# E-meter.net
KiCad netlist of a schematic drawn in EAGLE
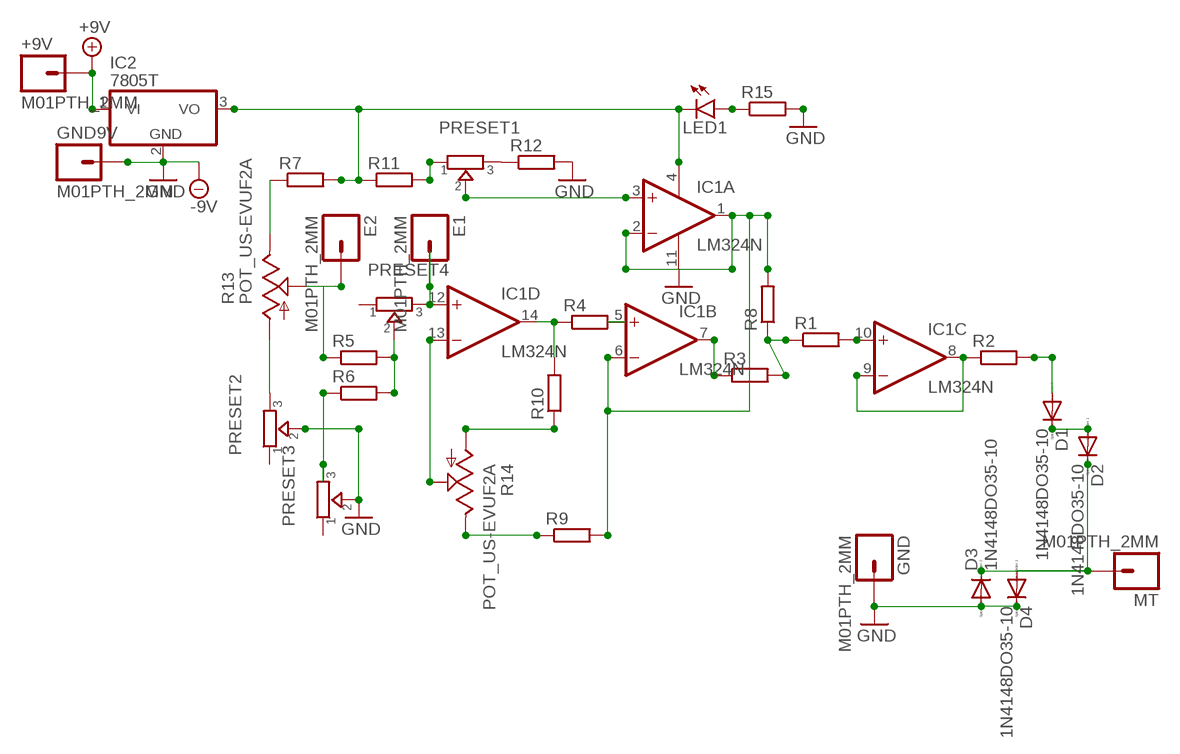
[diagram p0: schematic, sheet 1]

(export (version "E")
  (design (tool "Eeschema 10.0.6"))
  (components
    (comp (ref "+9V")
      (value "M01PTH_2MM")
      (footprint "eagle-import:1X01_2MM")
      (libsource (lib "eagle-import") (part "M01PTH_2MM"))
    )
    (comp (ref "D1")
      (value "1N4148DO35-10")
      (footprint "eagle-import:DO35-10")
      (libsource (lib "eagle-import") (part "1N4148DO35-10"))
    )
    (comp (ref "D2")
      (value "1N4148DO35-10")
      (footprint "eagle-import:DO35-10")
      (libsource (lib "eagle-import") (part "1N4148DO35-10"))
    )
    (comp (ref "D3")
      (value "1N4148DO35-10")
      (footprint "eagle-import:DO35-10")
      (libsource (lib "eagle-import") (part "1N4148DO35-10"))
    )
    (comp (ref "D4")
      (value "1N4148DO35-10")
      (footprint "eagle-import:DO35-10")
      (libsource (lib "eagle-import") (part "1N4148DO35-10"))
    )
    (comp (ref "E1")
      (value "M01PTH_2MM")
      (footprint "eagle-import:1X01_2MM")
      (libsource (lib "eagle-import") (part "M01PTH_2MM"))
    )
    (comp (ref "E2")
      (value "M01PTH_2MM")
      (footprint "eagle-import:1X01_2MM")
      (libsource (lib "eagle-import") (part "M01PTH_2MM"))
    )
    (comp (ref "GND")
      (value "M01PTH_2MM")
      (footprint "eagle-import:1X01_2MM")
      (libsource (lib "eagle-import") (part "M01PTH_2MM"))
    )
    (comp (ref "GND9V")
      (value "M01PTH_2MM")
      (footprint "eagle-import:1X01_2MM")
      (libsource (lib "eagle-import") (part "M01PTH_2MM"))
    )
    (comp (ref "IC1")
      (value "LM324N")
      (footprint "eagle-import:DIL14")
      (libsource (lib "eagle-import") (part "LM324N"))
    )
    (comp (ref "IC2")
      (value "7805T")
      (footprint "eagle-import:TO220H")
      (libsource (lib "eagle-import") (part "78T05"))
    )
    (comp (ref "LED1")
      (value "LED5MM")
      (footprint "eagle-import:LED5MM")
      (libsource (lib "eagle-import") (part "LED5MM"))
    )
    (comp (ref "MT")
      (value "M01PTH_2MM")
      (footprint "eagle-import:1X01_2MM")
      (libsource (lib "eagle-import") (part "M01PTH_2MM"))
    )
    (comp (ref "PRESET1")
      (value "TRIMMER-3306F")
      (footprint "eagle-import:TRIMMER_3306F")
      (libsource (lib "eagle-import") (part "TRIMMER-3306F"))
    )
    (comp (ref "PRESET2")
      (value "TRIMMER-3306F")
      (footprint "eagle-import:TRIMMER_3306F")
      (libsource (lib "eagle-import") (part "TRIMMER-3306F"))
    )
    (comp (ref "PRESET3")
      (value "TRIMMER-3306F")
      (footprint "eagle-import:TRIMMER_3306F")
      (libsource (lib "eagle-import") (part "TRIMMER-3306F"))
    )
    (comp (ref "PRESET4")
      (value "TRIMMER-3306F")
      (footprint "eagle-import:TRIMMER_3306F")
      (libsource (lib "eagle-import") (part "TRIMMER-3306F"))
    )
    (comp (ref "R1")
      (value "R-EU_0207/10")
      (footprint "eagle-import:0207_10")
      (libsource (lib "eagle-import") (part "R-EU_0207/10"))
    )
    (comp (ref "R2")
      (value "R-EU_0207/10")
      (footprint "eagle-import:0207_10")
      (libsource (lib "eagle-import") (part "R-EU_0207/10"))
    )
    (comp (ref "R3")
      (value "R-EU_0207/10")
      (footprint "eagle-import:0207_10")
      (libsource (lib "eagle-import") (part "R-EU_0207/10"))
    )
    (comp (ref "R4")
      (value "R-EU_0207/10")
      (footprint "eagle-import:0207_10")
      (libsource (lib "eagle-import") (part "R-EU_0207/10"))
    )
    (comp (ref "R5")
      (value "R-EU_0207/10")
      (footprint "eagle-import:0207_10")
      (libsource (lib "eagle-import") (part "R-EU_0207/10"))
    )
    (comp (ref "R6")
      (value "R-EU_0207/10")
      (footprint "eagle-import:0207_10")
      (libsource (lib "eagle-import") (part "R-EU_0207/10"))
    )
    (comp (ref "R7")
      (value "R-EU_0207/10")
      (footprint "eagle-import:0207_10")
      (libsource (lib "eagle-import") (part "R-EU_0207/10"))
    )
    (comp (ref "R8")
      (value "R-EU_0207/10")
      (footprint "eagle-import:0207_10")
      (libsource (lib "eagle-import") (part "R-EU_0207/10"))
    )
    (comp (ref "R9")
      (value "R-EU_0207/10")
      (footprint "eagle-import:0207_10")
      (libsource (lib "eagle-import") (part "R-EU_0207/10"))
    )
    (comp (ref "R10")
      (value "R-EU_0207/10")
      (footprint "eagle-import:0207_10")
      (libsource (lib "eagle-import") (part "R-EU_0207/10"))
    )
    (comp (ref "R11")
      (value "R-EU_0207/10")
      (footprint "eagle-import:0207_10")
      (libsource (lib "eagle-import") (part "R-EU_0207/10"))
    )
    (comp (ref "R12")
      (value "R-EU_0207/10")
      (footprint "eagle-import:0207_10")
      (libsource (lib "eagle-import") (part "R-EU_0207/10"))
    )
    (comp (ref "R13")
      (value "POT_US-EVUF2A")
      (footprint "eagle-import:POT_EVUF")
      (libsource (lib "eagle-import") (part "POT_US-EVUAF2"))
    )
    (comp (ref "R14")
      (value "POT_US-EVUF2A")
      (footprint "eagle-import:POT_EVUF")
      (libsource (lib "eagle-import") (part "POT_US-EVUAF2"))
    )
    (comp (ref "R15")
      (value "R-EU_0207/10")
      (footprint "eagle-import:0207_10")
      (libsource (lib "eagle-import") (part "R-EU_0207/10"))
    )
  )
  (nets
    (net (code "1") (name "+9V") (class "Default")
      (node (ref "+9V") (pin "1") (pinfunction "1_1") (pintype "passive"))
      (node (ref "IC2") (pin "1") (pinfunction "VI_1") (pintype "input"))
    )
    (net (code "2") (name "-9V") (class "Default")
      (node (ref "D3") (pin "A") (pinfunction "A_A") (pintype "passive"))
      (node (ref "D4") (pin "C") (pinfunction "C_C") (pintype "passive"))
      (node (ref "GND") (pin "1") (pinfunction "1_1") (pintype "passive"))
      (node (ref "GND9V") (pin "1") (pinfunction "1_1") (pintype "passive"))
      (node (ref "IC1") (pin "11") (pinfunction "V-_11") (pintype "power_in"))
      (node (ref "IC2") (pin "2") (pinfunction "GND_2") (pintype "passive"))
      (node (ref "PRESET2") (pin "2") (pinfunction "2_2") (pintype "passive"))
      (node (ref "PRESET3") (pin "2") (pinfunction "2_2") (pintype "passive"))
      (node (ref "R12") (pin "2") (pinfunction "2_2") (pintype "passive"))
      (node (ref "R15") (pin "2") (pinfunction "2_2") (pintype "passive"))
    )
    (net (code "3") (name "Net-(D1-PadA)") (class "Default")
      (node (ref "D1") (pin "A") (pinfunction "A_A") (pintype "passive"))
      (node (ref "R2") (pin "2") (pinfunction "2_2") (pintype "passive"))
    )
    (net (code "4") (name "Net-(D1-PadC)") (class "Default")
      (node (ref "D1") (pin "C") (pinfunction "C_C") (pintype "passive"))
      (node (ref "D2") (pin "A") (pinfunction "A_A") (pintype "passive"))
    )
    (net (code "5") (name "Net-(D2-PadC)") (class "Default")
      (node (ref "D2") (pin "C") (pinfunction "C_C") (pintype "passive"))
      (node (ref "D3") (pin "C") (pinfunction "C_C") (pintype "passive"))
      (node (ref "D4") (pin "A") (pinfunction "A_A") (pintype "passive"))
      (node (ref "MT") (pin "1") (pinfunction "1_1") (pintype "passive"))
    )
    (net (code "6") (name "Net-(IC1A-+IN)") (class "Default")
      (node (ref "IC1") (pin "3") (pinfunction "+IN_3") (pintype "input"))
      (node (ref "PRESET1") (pin "2") (pinfunction "2_2") (pintype "passive"))
    )
    (net (code "7") (name "Net-(IC1A--IN)") (class "Default")
      (node (ref "IC1") (pin "1") (pinfunction "OUT_1") (pintype "output"))
      (node (ref "IC1") (pin "2") (pinfunction "-IN_2") (pintype "input"))
      (node (ref "IC1") (pin "6") (pinfunction "-IN_6") (pintype "input"))
      (node (ref "R8") (pin "2") (pinfunction "2_2") (pintype "passive"))
      (node (ref "R9") (pin "2") (pinfunction "2_2") (pintype "passive"))
    )
    (net (code "8") (name "Net-(IC1B-+IN)") (class "Default")
      (node (ref "IC1") (pin "5") (pinfunction "+IN_5") (pintype "input"))
      (node (ref "R4") (pin "2") (pinfunction "2_2") (pintype "passive"))
    )
    (net (code "9") (name "Net-(IC1B-OUT)") (class "Default")
      (node (ref "IC1") (pin "7") (pinfunction "OUT_7") (pintype "output"))
      (node (ref "R3") (pin "1") (pinfunction "1_1") (pintype "passive"))
    )
    (net (code "10") (name "Net-(IC1C-+IN)") (class "Default")
      (node (ref "IC1") (pin "10") (pinfunction "+IN_10") (pintype "input"))
      (node (ref "R1") (pin "2") (pinfunction "2_2") (pintype "passive"))
    )
    (net (code "11") (name "Net-(IC1C--IN)") (class "Default")
      (node (ref "IC1") (pin "8") (pinfunction "OUT_8") (pintype "output"))
      (node (ref "IC1") (pin "9") (pinfunction "-IN_9") (pintype "input"))
      (node (ref "R2") (pin "1") (pinfunction "1_1") (pintype "passive"))
    )
    (net (code "12") (name "Net-(IC1D-+IN)") (class "Default")
      (node (ref "E1") (pin "1") (pinfunction "1_1") (pintype "passive"))
      (node (ref "IC1") (pin "12") (pinfunction "+IN_12") (pintype "input"))
      (node (ref "PRESET4") (pin "3") (pinfunction "3_3") (pintype "passive"))
    )
    (net (code "13") (name "Net-(IC1D--IN)") (class "Default")
      (node (ref "IC1") (pin "13") (pinfunction "-IN_13") (pintype "input"))
      (node (ref "R14") (pin "2") (pinfunction "S_2") (pintype "passive"))
    )
    (net (code "14") (name "Net-(IC1D-OUT)") (class "Default")
      (node (ref "IC1") (pin "14") (pinfunction "OUT_14") (pintype "output"))
      (node (ref "R10") (pin "2") (pinfunction "2_2") (pintype "passive"))
      (node (ref "R4") (pin "1") (pinfunction "1_1") (pintype "passive"))
    )
    (net (code "15") (name "Net-(IC1E-V+)") (class "Default")
      (node (ref "IC1") (pin "4") (pinfunction "V+_4") (pintype "power_in"))
      (node (ref "IC2") (pin "3") (pinfunction "VO_3") (pintype "passive"))
      (node (ref "LED1") (pin "K") (pinfunction "C_K") (pintype "passive"))
      (node (ref "R11") (pin "1") (pinfunction "1_1") (pintype "passive"))
      (node (ref "R7") (pin "2") (pinfunction "2_2") (pintype "passive"))
    )
    (net (code "16") (name "Net-(LED1-PadA)") (class "Default")
      (node (ref "LED1") (pin "A") (pinfunction "A_A") (pintype "passive"))
      (node (ref "R15") (pin "1") (pinfunction "1_1") (pintype "passive"))
    )
    (net (code "17") (name "Net-(PRESET1-Pad1)") (class "Default")
      (node (ref "PRESET1") (pin "1") (pinfunction "1_1") (pintype "passive"))
      (node (ref "R11") (pin "2") (pinfunction "2_2") (pintype "passive"))
    )
    (net (code "18") (name "Net-(PRESET1-Pad3)") (class "Default")
      (node (ref "PRESET1") (pin "3") (pinfunction "3_3") (pintype "passive"))
      (node (ref "R12") (pin "1") (pinfunction "1_1") (pintype "passive"))
    )
    (net (code "19") (name "Net-(PRESET3-Pad3)") (class "Default")
      (node (ref "PRESET3") (pin "3") (pinfunction "3_3") (pintype "passive"))
      (node (ref "R6") (pin "1") (pinfunction "1_1") (pintype "passive"))
    )
    (net (code "20") (name "Net-(PRESET4-Pad2)") (class "Default")
      (node (ref "PRESET4") (pin "2") (pinfunction "2_2") (pintype "passive"))
      (node (ref "R5") (pin "2") (pinfunction "2_2") (pintype "passive"))
      (node (ref "R6") (pin "2") (pinfunction "2_2") (pintype "passive"))
    )
    (net (code "21") (name "Net-(R1-Pad1)") (class "Default")
      (node (ref "R1") (pin "1") (pinfunction "1_1") (pintype "passive"))
      (node (ref "R3") (pin "2") (pinfunction "2_2") (pintype "passive"))
      (node (ref "R8") (pin "1") (pinfunction "1_1") (pintype "passive"))
    )
    (net (code "22") (name "Net-(R13-A)") (class "Default")
      (node (ref "PRESET2") (pin "3") (pinfunction "3_3") (pintype "passive"))
      (node (ref "R13") (pin "1") (pinfunction "A_1") (pintype "passive"))
    )
    (net (code "23") (name "Net-(R13-E)") (class "Default")
      (node (ref "R13") (pin "3") (pinfunction "E_3") (pintype "passive"))
      (node (ref "R7") (pin "1") (pinfunction "1_1") (pintype "passive"))
    )
    (net (code "24") (name "Net-(R13-S)") (class "Default")
      (node (ref "E2") (pin "1") (pinfunction "1_1") (pintype "passive"))
      (node (ref "R13") (pin "2") (pinfunction "S_2") (pintype "passive"))
      (node (ref "R5") (pin "1") (pinfunction "1_1") (pintype "passive"))
    )
    (net (code "25") (name "Net-(R14-A)") (class "Default")
      (node (ref "R10") (pin "1") (pinfunction "1_1") (pintype "passive"))
      (node (ref "R14") (pin "1") (pinfunction "A_1") (pintype "passive"))
    )
    (net (code "26") (name "Net-(R14-E)") (class "Default")
      (node (ref "R14") (pin "3") (pinfunction "E_3") (pintype "passive"))
      (node (ref "R9") (pin "1") (pinfunction "1_1") (pintype "passive"))
    )
    (net (code "27") (name "unconnected-(PRESET2-Pad1)") (class "Default")
      (node (ref "PRESET2") (pin "1") (pinfunction "1_1") (pintype "passive"))
    )
    (net (code "28") (name "unconnected-(PRESET3-Pad1)") (class "Default")
      (node (ref "PRESET3") (pin "1") (pinfunction "1_1") (pintype "passive"))
    )
    (net (code "29") (name "unconnected-(PRESET4-Pad1)") (class "Default")
      (node (ref "PRESET4") (pin "1") (pinfunction "1_1") (pintype "passive"))
    )
  )
)
